# Sheet.net
KiCad netlist of a schematic drawn in Altium Designer
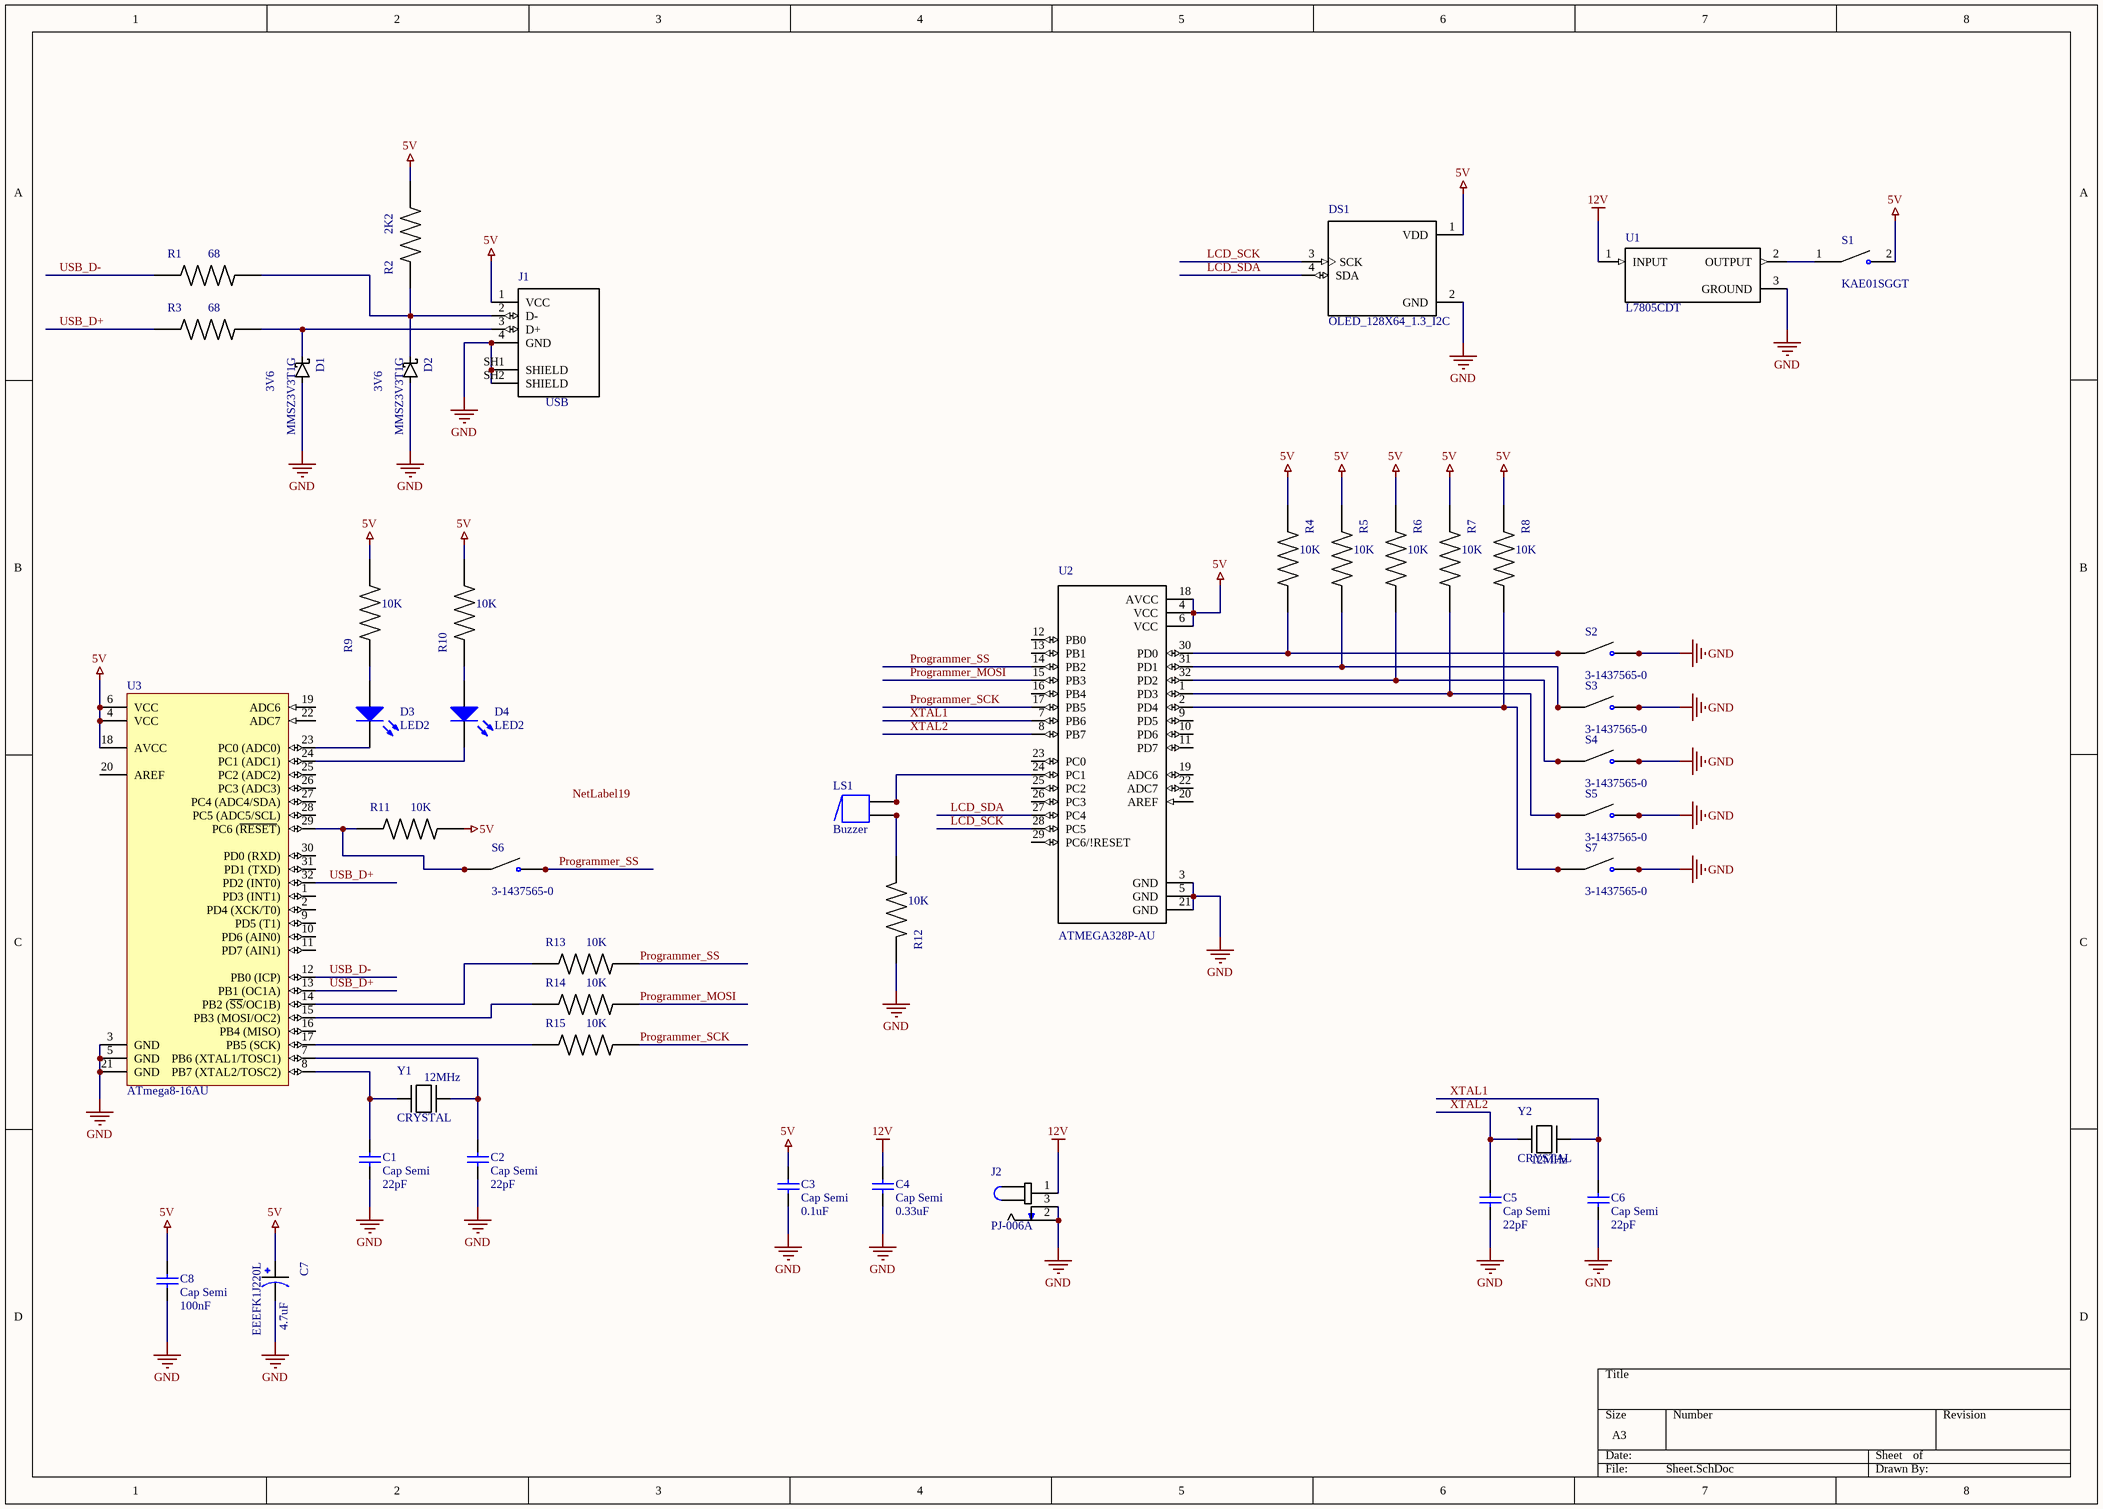
[diagram p0: Sheet.SchDoc]

(export (version "E")
  (design (tool "Eeschema 10.0.6"))
  (components
    (comp (ref "C1")
      (value "Cap Semi")
      (footprint "C1206")
      (description "Capacitor (Semiconductor SIM Model)")
      (fields (field (name "ALTIUM_VALUE") "22pF") (field (name "PUBLISHER") "Altium Limited"))
      (libsource (lib "Miscellaneous Devices") (part "Cap Semi"))
    )
    (comp (ref "C2")
      (value "Cap Semi")
      (footprint "C1206")
      (description "Capacitor (Semiconductor SIM Model)")
      (fields (field (name "ALTIUM_VALUE") "22pF") (field (name "PUBLISHER") "Altium Limited"))
      (libsource (lib "Miscellaneous Devices") (part "Cap Semi"))
    )
    (comp (ref "C3")
      (value "Cap Semi")
      (footprint "C1206")
      (description "Capacitor (Semiconductor SIM Model)")
      (fields (field (name "ALTIUM_VALUE") "0.1uF") (field (name "PUBLISHER") "Altium Limited"))
      (libsource (lib "Miscellaneous Devices") (part "Cap Semi"))
    )
    (comp (ref "C4")
      (value "Cap Semi")
      (footprint "C1206")
      (description "Capacitor (Semiconductor SIM Model)")
      (fields (field (name "ALTIUM_VALUE") "0.33uF") (field (name "PUBLISHER") "Altium Limited"))
      (libsource (lib "Miscellaneous Devices") (part "Cap Semi"))
    )
    (comp (ref "C5")
      (value "Cap Semi")
      (footprint "C1206")
      (description "Capacitor (Semiconductor SIM Model)")
      (fields (field (name "ALTIUM_VALUE") "22pF") (field (name "PUBLISHER") "Altium Limited"))
      (libsource (lib "Miscellaneous Devices") (part "Cap Semi"))
    )
    (comp (ref "C6")
      (value "Cap Semi")
      (footprint "C1206")
      (description "Capacitor (Semiconductor SIM Model)")
      (fields (field (name "ALTIUM_VALUE") "22pF") (field (name "PUBLISHER") "Altium Limited"))
      (libsource (lib "Miscellaneous Devices") (part "Cap Semi"))
    )
    (comp (ref "C7")
      (value "EEEFK1J220L")
      (footprint "*CAP_EEEFK1J220L")
      (description "CAP ALUM 22UF 20% 63V SMD")
      (fields (field (name "MF") "Panasonic") (field (name "ALTIUM_VALUE") "4.7uF"))
      (libsource (lib "EEEFK1J220L") (part "EEEFK1J220L"))
    )
    (comp (ref "C8")
      (value "Cap Semi")
      (footprint "C1206")
      (description "Capacitor (Semiconductor SIM Model)")
      (fields (field (name "ALTIUM_VALUE") "100nF") (field (name "PUBLISHER") "Altium Limited"))
      (libsource (lib "Miscellaneous Devices") (part "Cap Semi"))
    )
    (comp (ref "D1")
      (value "MMSZ3V3T1G")
      (footprint "*MMSZ5V6T1G_MMSZ3V3T1G(Primary)")
      (description "Zener Diode 3.3 V 500 mW Â±5% Surface Mount SOD-123")
      (fields (field (name "MF") "ON Semiconductor") (field (name "ALTIUM_VALUE") "3V6"))
      (libsource (lib "MMSZ3V3T1G") (part "MMSZ3V3T1G"))
    )
    (comp (ref "D2")
      (value "MMSZ3V3T1G")
      (footprint "*MMSZ5V6T1G_MMSZ3V3T1G(Primary)")
      (description "Zener Diode 3.3 V 500 mW Â±5% Surface Mount SOD-123")
      (fields (field (name "MF") "ON Semiconductor") (field (name "ALTIUM_VALUE") "3V6"))
      (libsource (lib "MMSZ3V3T1G") (part "MMSZ3V3T1G"))
    )
    (comp (ref "D3")
      (value "LED2")
      (footprint "3.2X1.6X1.1")
      (description "Typical RED, GREEN, YELLOW, AMBER GaAs LED")
      (fields (field (name "PUBLISHER") "Altium Limited"))
      (libsource (lib "Miscellaneous Devices") (part "LED2"))
    )
    (comp (ref "D4")
      (value "LED2")
      (footprint "3.2X1.6X1.1")
      (description "Typical RED, GREEN, YELLOW, AMBER GaAs LED")
      (fields (field (name "PUBLISHER") "Altium Limited"))
      (libsource (lib "Miscellaneous Devices") (part "LED2"))
    )
    (comp (ref "DS1")
      (value "OLED_128X64_1.3_I2C")
      (footprint "*LCD_OLED_128X64_1.3_I2C")
      (fields
        (field (name "MF") "UNIVERSAL-SOLDER Electronics Ltd")
        (field (name "MP") "OLED 128x64 1.3&quot; I2C")
      )
      (libsource (lib "OLED_128X64_1.3_I2C") (part "OLED_128X64_1.3_I2C"))
    )
    (comp (ref "J1")
      (value "USB")
      (footprint "*GCT_USB1046-GF-0190-L-B-A_REVB4_USB1046-GF-0190-L-B-A_REVB4(Primary)")
      (description "USB-A (USB TYPE-A) USB 2.0 Receptacle Connector 4 Position Surface Mount, Through Hole")
      (fields (field (name "MF") "Global Connector Technology") (field (name "MP") "USB1046-GF-0190-L-B-A"))
      (libsource (lib "USB1046-GF-0190-L-B-A_REVB4") (part "USB1046-GF-0190-L-B-A_REVB4"))
    )
    (comp (ref "J2")
      (value "PJ-006A")
      (footprint "*CUI_PJ-006A")
      (description "2.0 x 6.3 mm, 2.0 A, Vertical, Through Hole, Dc Power Jack Connector")
      (fields (field (name "MF") "Same Sky"))
      (libsource (lib "PJ-006A") (part "PJ-006A"))
    )
    (comp (ref "LS1")
      (value "Buzzer")
      (footprint "ABSM-1574")
      (description "Magnetic Transducer Buzzer")
      (fields (field (name "PUBLISHER") "Altium Limited"))
      (libsource (lib "Miscellaneous Devices") (part "Buzzer"))
    )
    (comp (ref "R1")
      (value "68")
      (footprint "*RESC3115X65N")
      (description "Fixed Resistor CRGCQ 1206 120R 1%")
      (fields (field (name "MF") "TE Connectivity") (field (name "MP") "CRGCQ1206F120R"))
      (libsource (lib "CRGCQ1206F120R") (part "CRGCQ1206F120R"))
    )
    (comp (ref "R2")
      (value "2K2")
      (footprint "*RESC3115X65N")
      (description "Fixed Resistor CRGCQ 1206 120R 1%")
      (fields (field (name "MF") "TE Connectivity") (field (name "MP") "CRGCQ1206F120R"))
      (libsource (lib "CRGCQ1206F120R") (part "CRGCQ1206F120R"))
    )
    (comp (ref "R3")
      (value "68")
      (footprint "*RESC3115X65N")
      (description "Fixed Resistor CRGCQ 1206 120R 1%")
      (fields (field (name "MF") "TE Connectivity") (field (name "MP") "CRGCQ1206F120R"))
      (libsource (lib "CRGCQ1206F120R") (part "CRGCQ1206F120R"))
    )
    (comp (ref "R4")
      (value "10K")
      (footprint "*RESC3115X65N")
      (description "Fixed Resistor CRGCQ 1206 120R 1%")
      (fields (field (name "MF") "TE Connectivity") (field (name "MP") "CRGCQ1206F120R"))
      (libsource (lib "CRGCQ1206F120R") (part "CRGCQ1206F120R"))
    )
    (comp (ref "R5")
      (value "10K")
      (footprint "*RESC3115X65N")
      (description "Fixed Resistor CRGCQ 1206 120R 1%")
      (fields (field (name "MF") "TE Connectivity") (field (name "MP") "CRGCQ1206F120R"))
      (libsource (lib "CRGCQ1206F120R") (part "CRGCQ1206F120R"))
    )
    (comp (ref "R6")
      (value "10K")
      (footprint "*RESC3115X65N")
      (description "Fixed Resistor CRGCQ 1206 120R 1%")
      (fields (field (name "MF") "TE Connectivity") (field (name "MP") "CRGCQ1206F120R"))
      (libsource (lib "CRGCQ1206F120R") (part "CRGCQ1206F120R"))
    )
    (comp (ref "R7")
      (value "10K")
      (footprint "*RESC3115X65N")
      (description "Fixed Resistor CRGCQ 1206 120R 1%")
      (fields (field (name "MF") "TE Connectivity") (field (name "MP") "CRGCQ1206F120R"))
      (libsource (lib "CRGCQ1206F120R") (part "CRGCQ1206F120R"))
    )
    (comp (ref "R8")
      (value "10K")
      (footprint "*RESC3115X65N")
      (description "Fixed Resistor CRGCQ 1206 120R 1%")
      (fields (field (name "MF") "TE Connectivity") (field (name "MP") "CRGCQ1206F120R"))
      (libsource (lib "CRGCQ1206F120R") (part "CRGCQ1206F120R"))
    )
    (comp (ref "R9")
      (value "10K")
      (footprint "*RESC3115X65N")
      (description "Fixed Resistor CRGCQ 1206 120R 1%")
      (fields (field (name "MF") "TE Connectivity") (field (name "MP") "CRGCQ1206F120R"))
      (libsource (lib "CRGCQ1206F120R") (part "CRGCQ1206F120R"))
    )
    (comp (ref "R10")
      (value "10K")
      (footprint "*RESC3115X65N")
      (description "Fixed Resistor CRGCQ 1206 120R 1%")
      (fields (field (name "MF") "TE Connectivity") (field (name "MP") "CRGCQ1206F120R"))
      (libsource (lib "CRGCQ1206F120R") (part "CRGCQ1206F120R"))
    )
    (comp (ref "R11")
      (value "10K")
      (footprint "*RESC3115X65N")
      (description "Fixed Resistor CRGCQ 1206 120R 1%")
      (fields (field (name "MF") "TE Connectivity") (field (name "MP") "CRGCQ1206F120R"))
      (libsource (lib "CRGCQ1206F120R") (part "CRGCQ1206F120R"))
    )
    (comp (ref "R12")
      (value "10K")
      (footprint "*RESC3115X65N")
      (description "Fixed Resistor CRGCQ 1206 120R 1%")
      (fields (field (name "MF") "TE Connectivity") (field (name "MP") "CRGCQ1206F120R"))
      (libsource (lib "CRGCQ1206F120R") (part "CRGCQ1206F120R"))
    )
    (comp (ref "R13")
      (value "10K")
      (footprint "*RESC3115X65N")
      (description "Fixed Resistor CRGCQ 1206 120R 1%")
      (fields (field (name "MF") "TE Connectivity") (field (name "MP") "CRGCQ1206F120R"))
      (libsource (lib "CRGCQ1206F120R") (part "CRGCQ1206F120R"))
    )
    (comp (ref "R14")
      (value "10K")
      (footprint "*RESC3115X65N")
      (description "Fixed Resistor CRGCQ 1206 120R 1%")
      (fields (field (name "MF") "TE Connectivity") (field (name "MP") "CRGCQ1206F120R"))
      (libsource (lib "CRGCQ1206F120R") (part "CRGCQ1206F120R"))
    )
    (comp (ref "R15")
      (value "10K")
      (footprint "*RESC3115X65N")
      (description "Fixed Resistor CRGCQ 1206 120R 1%")
      (fields (field (name "MF") "TE Connectivity") (field (name "MP") "CRGCQ1206F120R"))
      (libsource (lib "CRGCQ1206F120R") (part "CRGCQ1206F120R"))
    )
    (comp (ref "S1")
      (value "KAE01SGGT")
      (footprint "*SW_KAE01SGGT")
      (description "Dip Switch SPST 1 Position Surface Mount Slide (Standard) Actuator 25mA 24VDC")
      (fields (field (name "MF") "E-Switch"))
      (libsource (lib "KAE01SGGT") (part "KAE01SGGT"))
    )
    (comp (ref "S2")
      (value "3-1437565-0")
      (footprint "*SW_3-1437565-0")
      (description "Switch Tactile OFF (ON) SPST Round Button Gull Wing 0.05A 24VDC 1VA 9.18N SMD T/R")
      (fields (field (name "MF") "TE Connectivity") (field (name "MP") "314375650"))
      (libsource (lib "3-1437565-0") (part "3-1437565-0"))
    )
    (comp (ref "S3")
      (value "3-1437565-0")
      (footprint "*SW_3-1437565-0")
      (description "Switch Tactile OFF (ON) SPST Round Button Gull Wing 0.05A 24VDC 1VA 9.18N SMD T/R")
      (fields (field (name "MF") "TE Connectivity") (field (name "MP") "314375650"))
      (libsource (lib "3-1437565-0") (part "3-1437565-0"))
    )
    (comp (ref "S4")
      (value "3-1437565-0")
      (footprint "*SW_3-1437565-0")
      (description "Switch Tactile OFF (ON) SPST Round Button Gull Wing 0.05A 24VDC 1VA 9.18N SMD T/R")
      (fields (field (name "MF") "TE Connectivity") (field (name "MP") "314375650"))
      (libsource (lib "3-1437565-0") (part "3-1437565-0"))
    )
    (comp (ref "S5")
      (value "3-1437565-0")
      (footprint "*SW_3-1437565-0")
      (description "Switch Tactile OFF (ON) SPST Round Button Gull Wing 0.05A 24VDC 1VA 9.18N SMD T/R")
      (fields (field (name "MF") "TE Connectivity") (field (name "MP") "314375650"))
      (libsource (lib "3-1437565-0") (part "3-1437565-0"))
    )
    (comp (ref "S6")
      (value "3-1437565-0")
      (footprint "*SW_3-1437565-0")
      (description "Switch Tactile OFF (ON) SPST Round Button Gull Wing 0.05A 24VDC 1VA 9.18N SMD T/R")
      (fields (field (name "MF") "TE Connectivity") (field (name "MP") "314375650"))
      (libsource (lib "3-1437565-0") (part "3-1437565-0"))
    )
    (comp (ref "S7")
      (value "3-1437565-0")
      (footprint "*SW_3-1437565-0")
      (description "Switch Tactile OFF (ON) SPST Round Button Gull Wing 0.05A 24VDC 1VA 9.18N SMD T/R")
      (fields (field (name "MF") "TE Connectivity") (field (name "MP") "314375650"))
      (libsource (lib "3-1437565-0") (part "3-1437565-0"))
    )
    (comp (ref "U1")
      (value "L7805CDT")
      (footprint "*VREG_L7805CDT")
      (description "Linear Voltage Regulator IC Positive Fixed 1 Output  1.5A DPAK")
      (fields (field (name "MF") "STMicroelectronics"))
      (libsource (lib "L7805CDT") (part "L7805CDT"))
    )
    (comp (ref "U2")
      (value "ATMEGA328P-AU")
      (footprint "*QFP80P900X900X120-32N")
      (description "MCU 8-bit - AVR ATmega Family ATmega328 Series Microcontrollers - 20 MHz - 32 KB - 2 KB - 32 Pins.")
      (fields (field (name "DIGIKEY_PART_NUMBER") "ATMEGA328P-AU-ND") (field (name "MF") "MICROCHIP TECH."))
      (libsource (lib "ATMEGA328P-AU") (part "ATMEGA328P-AU"))
    )
    (comp (ref "U3")
      (value "ATmega8-16AU")
      (footprint "32A_M")
      (libsource (lib "Atmel Microcontroller megaAVR") (part "ATmega8-16AU"))
    )
    (comp (ref "Y1")
      (value "CRYSTAL")
      (footprint "*XTAL_CAA-12.000-20-3050-X-R")
      (description "12 MHz Â±30ppm Crystal 20pF 50 Ohms HC-49/US")
      (fields
        (field (name "MF") "Aker Technology Corp")
        (field (name "MP") "CAA-12.000-20-3050-X-R")
        (field (name "ALTIUM_VALUE") "12MHz")
      )
      (libsource (lib "CAA-12.000-20-3050-X-R") (part "CAA-12.000-20-3050-X-R"))
    )
    (comp (ref "Y2")
      (value "CRYSTAL")
      (footprint "*XTAL_CAA-12.000-20-3050-X-R")
      (description "12 MHz Â±30ppm Crystal 20pF 50 Ohms HC-49/US")
      (fields
        (field (name "MF") "Aker Technology Corp")
        (field (name "MP") "CAA-12.000-20-3050-X-R")
        (field (name "ALTIUM_VALUE") "12MHz")
      )
      (libsource (lib "CAA-12.000-20-3050-X-R") (part "CAA-12.000-20-3050-X-R"))
    )
  )
  (nets
    (net (code "1") (name "/LCD_SCK") (class "Default")
      (node (ref "DS1") (pin "3") (pinfunction "SCK_3") (pintype "input"))
      (node (ref "U2") (pin "28") (pinfunction "PC5_28") (pintype "bidirectional"))
    )
    (net (code "2") (name "/LCD_SDA") (class "Default")
      (node (ref "DS1") (pin "4") (pinfunction "SDA_4") (pintype "bidirectional"))
      (node (ref "U2") (pin "27") (pinfunction "PC4_27") (pintype "bidirectional"))
    )
    (net (code "4") (name "/Programmer_MOSI") (class "Default")
      (node (ref "R14") (pin "2") (pinfunction "2_2") (pintype "passive"))
      (node (ref "U2") (pin "15") (pinfunction "PB3_15") (pintype "bidirectional"))
    )
    (net (code "5") (name "/Programmer_SCK") (class "Default")
      (node (ref "R15") (pin "2") (pinfunction "2_2") (pintype "passive"))
      (node (ref "U2") (pin "17") (pinfunction "PB5_17") (pintype "bidirectional"))
    )
    (net (code "6") (name "/Programmer_SS") (class "Default")
      (node (ref "R13") (pin "2") (pinfunction "2_2") (pintype "passive"))
      (node (ref "S6") (pin "3") (pinfunction "NO_3") (pintype "passive"))
      (node (ref "S6") (pin "4") (pinfunction "NO_4") (pintype "passive"))
      (node (ref "U2") (pin "14") (pinfunction "PB2_14") (pintype "bidirectional"))
    )
    (net (code "7") (name "/USB_D+") (class "Default")
      (node (ref "R3") (pin "1") (pinfunction "1_1") (pintype "passive"))
      (node (ref "U3") (pin "13") (pinfunction "PB1_(OC1A)_13") (pintype "bidirectional"))
      (node (ref "U3") (pin "32") (pinfunction "PD2_(INT0)_32") (pintype "bidirectional"))
    )
    (net (code "8") (name "/USB_D-") (class "Default")
      (node (ref "R1") (pin "1") (pinfunction "1_1") (pintype "passive"))
      (node (ref "U3") (pin "12") (pinfunction "PB0_(ICP)_12") (pintype "bidirectional"))
    )
    (net (code "9") (name "/XTAL1") (class "Default")
      (node (ref "C6") (pin "2") (pinfunction "2_2") (pintype "passive"))
      (node (ref "U2") (pin "7") (pinfunction "PB6_7") (pintype "bidirectional"))
      (node (ref "Y2") (pin "2") (pinfunction "2_2") (pintype "passive"))
    )
    (net (code "10") (name "/XTAL2") (class "Default")
      (node (ref "C5") (pin "2") (pinfunction "2_2") (pintype "passive"))
      (node (ref "U2") (pin "8") (pinfunction "PB7_8") (pintype "bidirectional"))
      (node (ref "Y2") (pin "1") (pinfunction "1_1") (pintype "passive"))
    )
    (net (code "11") (name "5V") (class "Default")
      (node (ref "C3") (pin "2") (pinfunction "2_2") (pintype "passive"))
      (node (ref "C7") (pin "1") (pinfunction "1_1") (pintype "passive"))
      (node (ref "C8") (pin "2") (pinfunction "2_2") (pintype "passive"))
      (node (ref "DS1") (pin "1") (pinfunction "VDD_1") (pintype "power_in"))
      (node (ref "J1") (pin "1") (pinfunction "VCC_1") (pintype "power_in"))
      (node (ref "R10") (pin "2") (pinfunction "2_2") (pintype "passive"))
      (node (ref "R11") (pin "2") (pinfunction "2_2") (pintype "passive"))
      (node (ref "R2") (pin "2") (pinfunction "2_2") (pintype "passive"))
      (node (ref "R4") (pin "1") (pinfunction "1_1") (pintype "passive"))
      (node (ref "R5") (pin "1") (pinfunction "1_1") (pintype "passive"))
      (node (ref "R6") (pin "1") (pinfunction "1_1") (pintype "passive"))
      (node (ref "R7") (pin "1") (pinfunction "1_1") (pintype "passive"))
      (node (ref "R8") (pin "1") (pinfunction "1_1") (pintype "passive"))
      (node (ref "R9") (pin "2") (pinfunction "2_2") (pintype "passive"))
      (node (ref "S1") (pin "2") (pinfunction "2_2") (pintype "passive"))
      (node (ref "U2") (pin "18") (pinfunction "AVCC_18") (pintype "power_in"))
      (node (ref "U2") (pin "4") (pinfunction "VCC_4") (pintype "power_in"))
      (node (ref "U2") (pin "6") (pinfunction "VCC_6") (pintype "power_in"))
      (node (ref "U3") (pin "18") (pinfunction "AVCC_18") (pintype "power_in"))
      (node (ref "U3") (pin "4") (pinfunction "VCC_4") (pintype "power_in"))
      (node (ref "U3") (pin "6") (pinfunction "VCC_6") (pintype "power_in"))
    )
    (net (code "12") (name "12V") (class "Default")
      (node (ref "C4") (pin "2") (pinfunction "2_2") (pintype "passive"))
      (node (ref "J2") (pin "1") (pinfunction "1_1") (pintype "passive"))
      (node (ref "U1") (pin "1") (pinfunction "INPUT_1") (pintype "input"))
    )
    (net (code "13") (name "GND") (class "Default")
      (node (ref "C1") (pin "1") (pinfunction "1_1") (pintype "passive"))
      (node (ref "C2") (pin "1") (pinfunction "1_1") (pintype "passive"))
      (node (ref "C3") (pin "1") (pinfunction "1_1") (pintype "passive"))
      (node (ref "C4") (pin "1") (pinfunction "1_1") (pintype "passive"))
      (node (ref "C5") (pin "1") (pinfunction "1_1") (pintype "passive"))
      (node (ref "C6") (pin "1") (pinfunction "1_1") (pintype "passive"))
      (node (ref "C7") (pin "2") (pinfunction "2_2") (pintype "passive"))
      (node (ref "C8") (pin "1") (pinfunction "1_1") (pintype "passive"))
      (node (ref "D1") (pin "A") (pinfunction "A_A") (pintype "passive"))
      (node (ref "D2") (pin "A") (pinfunction "A_A") (pintype "passive"))
      (node (ref "DS1") (pin "2") (pinfunction "GND_2") (pintype "power_in"))
      (node (ref "J1") (pin "4") (pinfunction "GND_4") (pintype "power_in"))
      (node (ref "J1") (pin "SH1") (pinfunction "SHIELD_SH1") (pintype "passive"))
      (node (ref "J1") (pin "SH2") (pinfunction "SHIELD_SH2") (pintype "passive"))
      (node (ref "J2") (pin "2") (pinfunction "2_2") (pintype "passive"))
      (node (ref "J2") (pin "3") (pinfunction "3_3") (pintype "passive"))
      (node (ref "R12") (pin "1") (pinfunction "1_1") (pintype "passive"))
      (node (ref "S2") (pin "3") (pinfunction "NO_3") (pintype "passive"))
      (node (ref "S2") (pin "4") (pinfunction "NO_4") (pintype "passive"))
      (node (ref "S3") (pin "3") (pinfunction "NO_3") (pintype "passive"))
      (node (ref "S3") (pin "4") (pinfunction "NO_4") (pintype "passive"))
      (node (ref "S4") (pin "3") (pinfunction "NO_3") (pintype "passive"))
      (node (ref "S4") (pin "4") (pinfunction "NO_4") (pintype "passive"))
      (node (ref "S5") (pin "3") (pinfunction "NO_3") (pintype "passive"))
      (node (ref "S5") (pin "4") (pinfunction "NO_4") (pintype "passive"))
      (node (ref "S7") (pin "3") (pinfunction "NO_3") (pintype "passive"))
      (node (ref "S7") (pin "4") (pinfunction "NO_4") (pintype "passive"))
      (node (ref "U1") (pin "3") (pinfunction "GROUND_3") (pintype "power_in"))
      (node (ref "U2") (pin "21") (pinfunction "GND_21") (pintype "power_in"))
      (node (ref "U2") (pin "3") (pinfunction "GND_3") (pintype "power_in"))
      (node (ref "U2") (pin "5") (pinfunction "GND_5") (pintype "power_in"))
      (node (ref "U3") (pin "21") (pinfunction "GND_21") (pintype "power_in"))
      (node (ref "U3") (pin "3") (pinfunction "GND_3") (pintype "power_in"))
      (node (ref "U3") (pin "5") (pinfunction "GND_5") (pintype "power_in"))
    )
    (net (code "14") (name "Net-(D3-A)") (class "Default")
      (node (ref "D3") (pin "1") (pinfunction "A_1") (pintype "passive"))
      (node (ref "R9") (pin "1") (pinfunction "1_1") (pintype "passive"))
    )
    (net (code "15") (name "Net-(D3-K)") (class "Default")
      (node (ref "D3") (pin "2") (pinfunction "K_2") (pintype "passive"))
      (node (ref "U3") (pin "23") (pinfunction "PC0_(ADC0)_23") (pintype "bidirectional"))
    )
    (net (code "16") (name "Net-(D4-A)") (class "Default")
      (node (ref "D4") (pin "1") (pinfunction "A_1") (pintype "passive"))
      (node (ref "R10") (pin "1") (pinfunction "1_1") (pintype "passive"))
    )
    (net (code "17") (name "Net-(D4-K)") (class "Default")
      (node (ref "D4") (pin "2") (pinfunction "K_2") (pintype "passive"))
      (node (ref "U3") (pin "24") (pinfunction "PC1_(ADC1)_24") (pintype "bidirectional"))
    )
    (net (code "18") (name "Net-(J1-D+)") (class "Default")
      (node (ref "D1") (pin "K") (pinfunction "K_K") (pintype "passive"))
      (node (ref "J1") (pin "3") (pinfunction "D+_3") (pintype "bidirectional"))
      (node (ref "R3") (pin "2") (pinfunction "2_2") (pintype "passive"))
    )
    (net (code "19") (name "Net-(J1-D-)") (class "Default")
      (node (ref "D2") (pin "K") (pinfunction "K_K") (pintype "passive"))
      (node (ref "J1") (pin "2") (pinfunction "D-_2") (pintype "bidirectional"))
      (node (ref "R1") (pin "2") (pinfunction "2_2") (pintype "passive"))
      (node (ref "R2") (pin "1") (pinfunction "1_1") (pintype "passive"))
    )
    (net (code "20") (name "Net-(LS1-Pad2)") (class "Default")
      (node (ref "LS1") (pin "2") (pinfunction "2_2") (pintype "passive"))
      (node (ref "LS1") (pin "2A") (pinfunction "2A_2A") (pintype "passive"))
      (node (ref "R12") (pin "2") (pinfunction "2_2") (pintype "passive"))
    )
    (net (code "21") (name "Net-(U1-OUTPUT)") (class "Default")
      (node (ref "S1") (pin "1") (pinfunction "1_1") (pintype "passive"))
      (node (ref "U1") (pin "2") (pinfunction "OUTPUT_2") (pintype "output"))
    )
    (net (code "22") (name "Net-(U2-PC1)") (class "Default")
      (node (ref "LS1") (pin "1") (pinfunction "1_1") (pintype "passive"))
      (node (ref "LS1") (pin "1A") (pinfunction "1A_1A") (pintype "passive"))
      (node (ref "U2") (pin "24") (pinfunction "PC1_24") (pintype "bidirectional"))
    )
    (net (code "23") (name "Net-(U2-PD0)") (class "Default")
      (node (ref "R4") (pin "2") (pinfunction "2_2") (pintype "passive"))
      (node (ref "S2") (pin "1") (pinfunction "COM_1") (pintype "passive"))
      (node (ref "S2") (pin "2") (pinfunction "COM_2") (pintype "passive"))
      (node (ref "U2") (pin "30") (pinfunction "PD0_30") (pintype "bidirectional"))
    )
    (net (code "24") (name "Net-(U2-PD1)") (class "Default")
      (node (ref "R5") (pin "2") (pinfunction "2_2") (pintype "passive"))
      (node (ref "S3") (pin "1") (pinfunction "COM_1") (pintype "passive"))
      (node (ref "S3") (pin "2") (pinfunction "COM_2") (pintype "passive"))
      (node (ref "U2") (pin "31") (pinfunction "PD1_31") (pintype "bidirectional"))
    )
    (net (code "25") (name "Net-(U2-PD2)") (class "Default")
      (node (ref "R6") (pin "2") (pinfunction "2_2") (pintype "passive"))
      (node (ref "S4") (pin "1") (pinfunction "COM_1") (pintype "passive"))
      (node (ref "S4") (pin "2") (pinfunction "COM_2") (pintype "passive"))
      (node (ref "U2") (pin "32") (pinfunction "PD2_32") (pintype "bidirectional"))
    )
    (net (code "26") (name "Net-(U2-PD3)") (class "Default")
      (node (ref "R7") (pin "2") (pinfunction "2_2") (pintype "passive"))
      (node (ref "S5") (pin "1") (pinfunction "COM_1") (pintype "passive"))
      (node (ref "S5") (pin "2") (pinfunction "COM_2") (pintype "passive"))
      (node (ref "U2") (pin "1") (pinfunction "PD3_1") (pintype "bidirectional"))
    )
    (net (code "27") (name "Net-(U2-PD4)") (class "Default")
      (node (ref "R8") (pin "2") (pinfunction "2_2") (pintype "passive"))
      (node (ref "S7") (pin "1") (pinfunction "COM_1") (pintype "passive"))
      (node (ref "S7") (pin "2") (pinfunction "COM_2") (pintype "passive"))
      (node (ref "U2") (pin "2") (pinfunction "PD4_2") (pintype "bidirectional"))
    )
    (net (code "28") (name "Net-(U3-PB2_(~{SS}{slash}OC1B))") (class "Default")
      (node (ref "R13") (pin "1") (pinfunction "1_1") (pintype "passive"))
      (node (ref "U3") (pin "14") (pinfunction "PB2_(~{SS}/OC1B)_14") (pintype "bidirectional"))
    )
    (net (code "29") (name "Net-(U3-PB3_(MOSI{slash}OC2))") (class "Default")
      (node (ref "R14") (pin "1") (pinfunction "1_1") (pintype "passive"))
      (node (ref "U3") (pin "15") (pinfunction "PB3_(MOSI/OC2)_15") (pintype "bidirectional"))
    )
    (net (code "30") (name "Net-(U3-PB5_(SCK))") (class "Default")
      (node (ref "R15") (pin "1") (pinfunction "1_1") (pintype "passive"))
      (node (ref "U3") (pin "17") (pinfunction "PB5_(SCK)_17") (pintype "bidirectional"))
    )
    (net (code "31") (name "Net-(U3-PB6_(XTAL1{slash}TOSC1))") (class "Default")
      (node (ref "C2") (pin "2") (pinfunction "2_2") (pintype "passive"))
      (node (ref "U3") (pin "7") (pinfunction "PB6_(XTAL1/TOSC1)_7") (pintype "bidirectional"))
      (node (ref "Y1") (pin "2") (pinfunction "2_2") (pintype "passive"))
    )
    (net (code "32") (name "Net-(U3-PB7_(XTAL2{slash}TOSC2))") (class "Default")
      (node (ref "C1") (pin "2") (pinfunction "2_2") (pintype "passive"))
      (node (ref "U3") (pin "8") (pinfunction "PB7_(XTAL2/TOSC2)_8") (pintype "bidirectional"))
      (node (ref "Y1") (pin "1") (pinfunction "1_1") (pintype "passive"))
    )
    (net (code "33") (name "Net-(U3-PC6_(~{RESET}))") (class "Default")
      (node (ref "R11") (pin "1") (pinfunction "1_1") (pintype "passive"))
      (node (ref "S6") (pin "1") (pinfunction "COM_1") (pintype "passive"))
      (node (ref "S6") (pin "2") (pinfunction "COM_2") (pintype "passive"))
      (node (ref "U3") (pin "29") (pinfunction "PC6_(~{RESET})_29") (pintype "bidirectional"))
    )
    (net (code "34") (name "unconnected-(U2-ADC6-Pad19)") (class "Default")
      (node (ref "U2") (pin "19") (pinfunction "ADC6_19") (pintype "bidirectional"))
    )
    (net (code "35") (name "unconnected-(U2-ADC7-Pad22)") (class "Default")
      (node (ref "U2") (pin "22") (pinfunction "ADC7_22") (pintype "bidirectional"))
    )
    (net (code "36") (name "unconnected-(U2-AREF-Pad20)") (class "Default")
      (node (ref "U2") (pin "20") (pinfunction "AREF_20") (pintype "input"))
    )
    (net (code "37") (name "unconnected-(U2-PB0-Pad12)") (class "Default")
      (node (ref "U2") (pin "12") (pinfunction "PB0_12") (pintype "bidirectional"))
    )
    (net (code "38") (name "unconnected-(U2-PB1-Pad13)") (class "Default")
      (node (ref "U2") (pin "13") (pinfunction "PB1_13") (pintype "bidirectional"))
    )
    (net (code "39") (name "unconnected-(U2-PB4-Pad16)") (class "Default")
      (node (ref "U2") (pin "16") (pinfunction "PB4_16") (pintype "bidirectional"))
    )
    (net (code "40") (name "unconnected-(U2-PC0-Pad23)") (class "Default")
      (node (ref "U2") (pin "23") (pinfunction "PC0_23") (pintype "bidirectional"))
    )
    (net (code "41") (name "unconnected-(U2-PC2-Pad25)") (class "Default")
      (node (ref "U2") (pin "25") (pinfunction "PC2_25") (pintype "bidirectional"))
    )
    (net (code "42") (name "unconnected-(U2-PC3-Pad26)") (class "Default")
      (node (ref "U2") (pin "26") (pinfunction "PC3_26") (pintype "bidirectional"))
    )
    (net (code "43") (name "unconnected-(U2-PC6{slash}!RESET-Pad29)") (class "Default")
      (node (ref "U2") (pin "29") (pinfunction "PC6/!RESET_29") (pintype "bidirectional"))
    )
    (net (code "44") (name "unconnected-(U2-PD5-Pad9)") (class "Default")
      (node (ref "U2") (pin "9") (pinfunction "PD5_9") (pintype "bidirectional"))
    )
    (net (code "45") (name "unconnected-(U2-PD6-Pad10)") (class "Default")
      (node (ref "U2") (pin "10") (pinfunction "PD6_10") (pintype "bidirectional"))
    )
    (net (code "46") (name "unconnected-(U2-PD7-Pad11)") (class "Default")
      (node (ref "U2") (pin "11") (pinfunction "PD7_11") (pintype "bidirectional"))
    )
    (net (code "47") (name "unconnected-(U3-ADC6-Pad19)") (class "Default")
      (node (ref "U3") (pin "19") (pinfunction "ADC6_19") (pintype "input"))
    )
    (net (code "48") (name "unconnected-(U3-ADC7-Pad22)") (class "Default")
      (node (ref "U3") (pin "22") (pinfunction "ADC7_22") (pintype "input"))
    )
    (net (code "49") (name "unconnected-(U3-AREF-Pad20)") (class "Default")
      (node (ref "U3") (pin "20") (pinfunction "AREF_20") (pintype "passive"))
    )
    (net (code "50") (name "unconnected-(U3-PB4_(MISO)-Pad16)") (class "Default")
      (node (ref "U3") (pin "16") (pinfunction "PB4_(MISO)_16") (pintype "bidirectional"))
    )
    (net (code "51") (name "unconnected-(U3-PC2_(ADC2)-Pad25)") (class "Default")
      (node (ref "U3") (pin "25") (pinfunction "PC2_(ADC2)_25") (pintype "bidirectional"))
    )
    (net (code "52") (name "unconnected-(U3-PC3_(ADC3)-Pad26)") (class "Default")
      (node (ref "U3") (pin "26") (pinfunction "PC3_(ADC3)_26") (pintype "bidirectional"))
    )
    (net (code "53") (name "unconnected-(U3-PC4_(ADC4{slash}SDA)-Pad27)") (class "Default")
      (node (ref "U3") (pin "27") (pinfunction "PC4_(ADC4/SDA)_27") (pintype "bidirectional"))
    )
    (net (code "54") (name "unconnected-(U3-PC5_(ADC5{slash}SCL)-Pad28)") (class "Default")
      (node (ref "U3") (pin "28") (pinfunction "PC5_(ADC5/SCL)_28") (pintype "bidirectional"))
    )
    (net (code "55") (name "unconnected-(U3-PD0_(RXD)-Pad30)") (class "Default")
      (node (ref "U3") (pin "30") (pinfunction "PD0_(RXD)_30") (pintype "bidirectional"))
    )
    (net (code "56") (name "unconnected-(U3-PD1_(TXD)-Pad31)") (class "Default")
      (node (ref "U3") (pin "31") (pinfunction "PD1_(TXD)_31") (pintype "bidirectional"))
    )
    (net (code "57") (name "unconnected-(U3-PD3_(INT1)-Pad1)") (class "Default")
      (node (ref "U3") (pin "1") (pinfunction "PD3_(INT1)_1") (pintype "bidirectional"))
    )
    (net (code "58") (name "unconnected-(U3-PD4_(XCK{slash}T0)-Pad2)") (class "Default")
      (node (ref "U3") (pin "2") (pinfunction "PD4_(XCK/T0)_2") (pintype "bidirectional"))
    )
    (net (code "59") (name "unconnected-(U3-PD5_(T1)-Pad9)") (class "Default")
      (node (ref "U3") (pin "9") (pinfunction "PD5_(T1)_9") (pintype "bidirectional"))
    )
    (net (code "60") (name "unconnected-(U3-PD6_(AIN0)-Pad10)") (class "Default")
      (node (ref "U3") (pin "10") (pinfunction "PD6_(AIN0)_10") (pintype "bidirectional"))
    )
    (net (code "61") (name "unconnected-(U3-PD7_(AIN1)-Pad11)") (class "Default")
      (node (ref "U3") (pin "11") (pinfunction "PD7_(AIN1)_11") (pintype "bidirectional"))
    )
  )
)
